# mimic4218.net
KiCad netlist of a schematic drawn in EAGLE
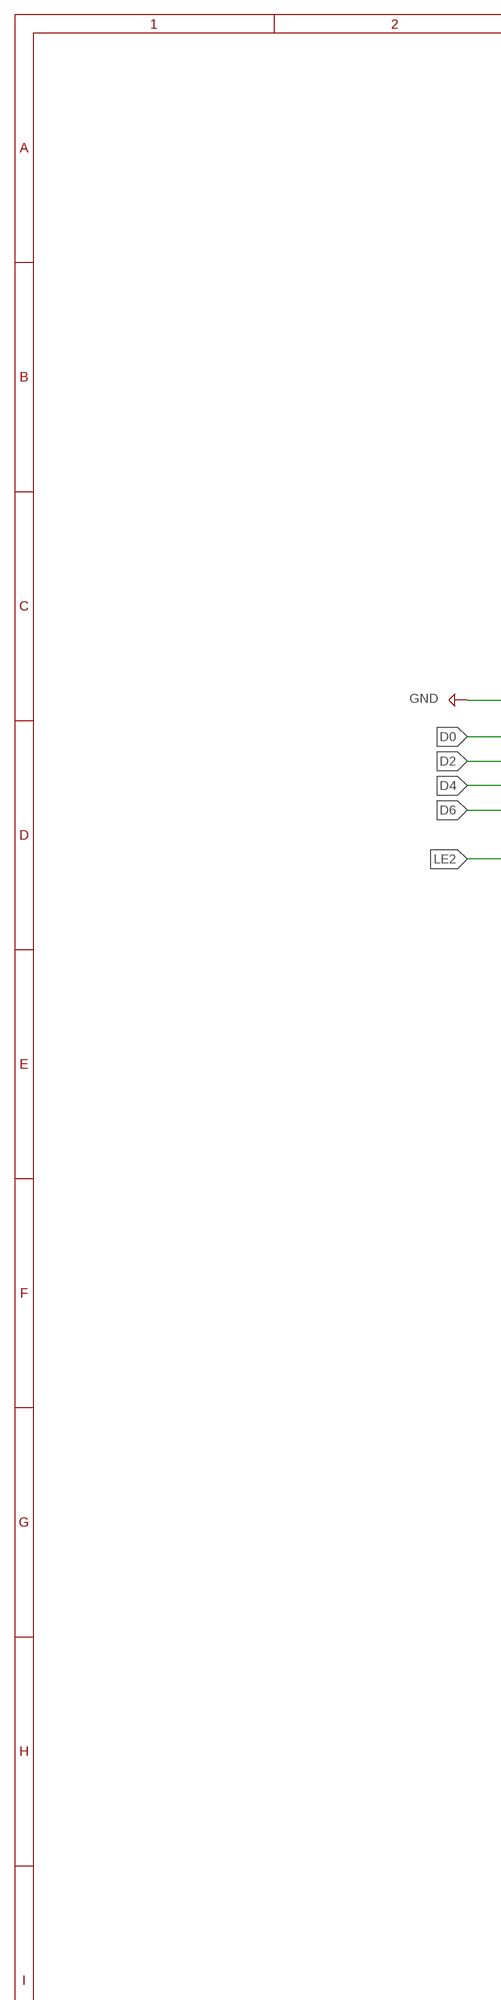
[diagram p0: schematic, sheet 1, part 1 of 2]
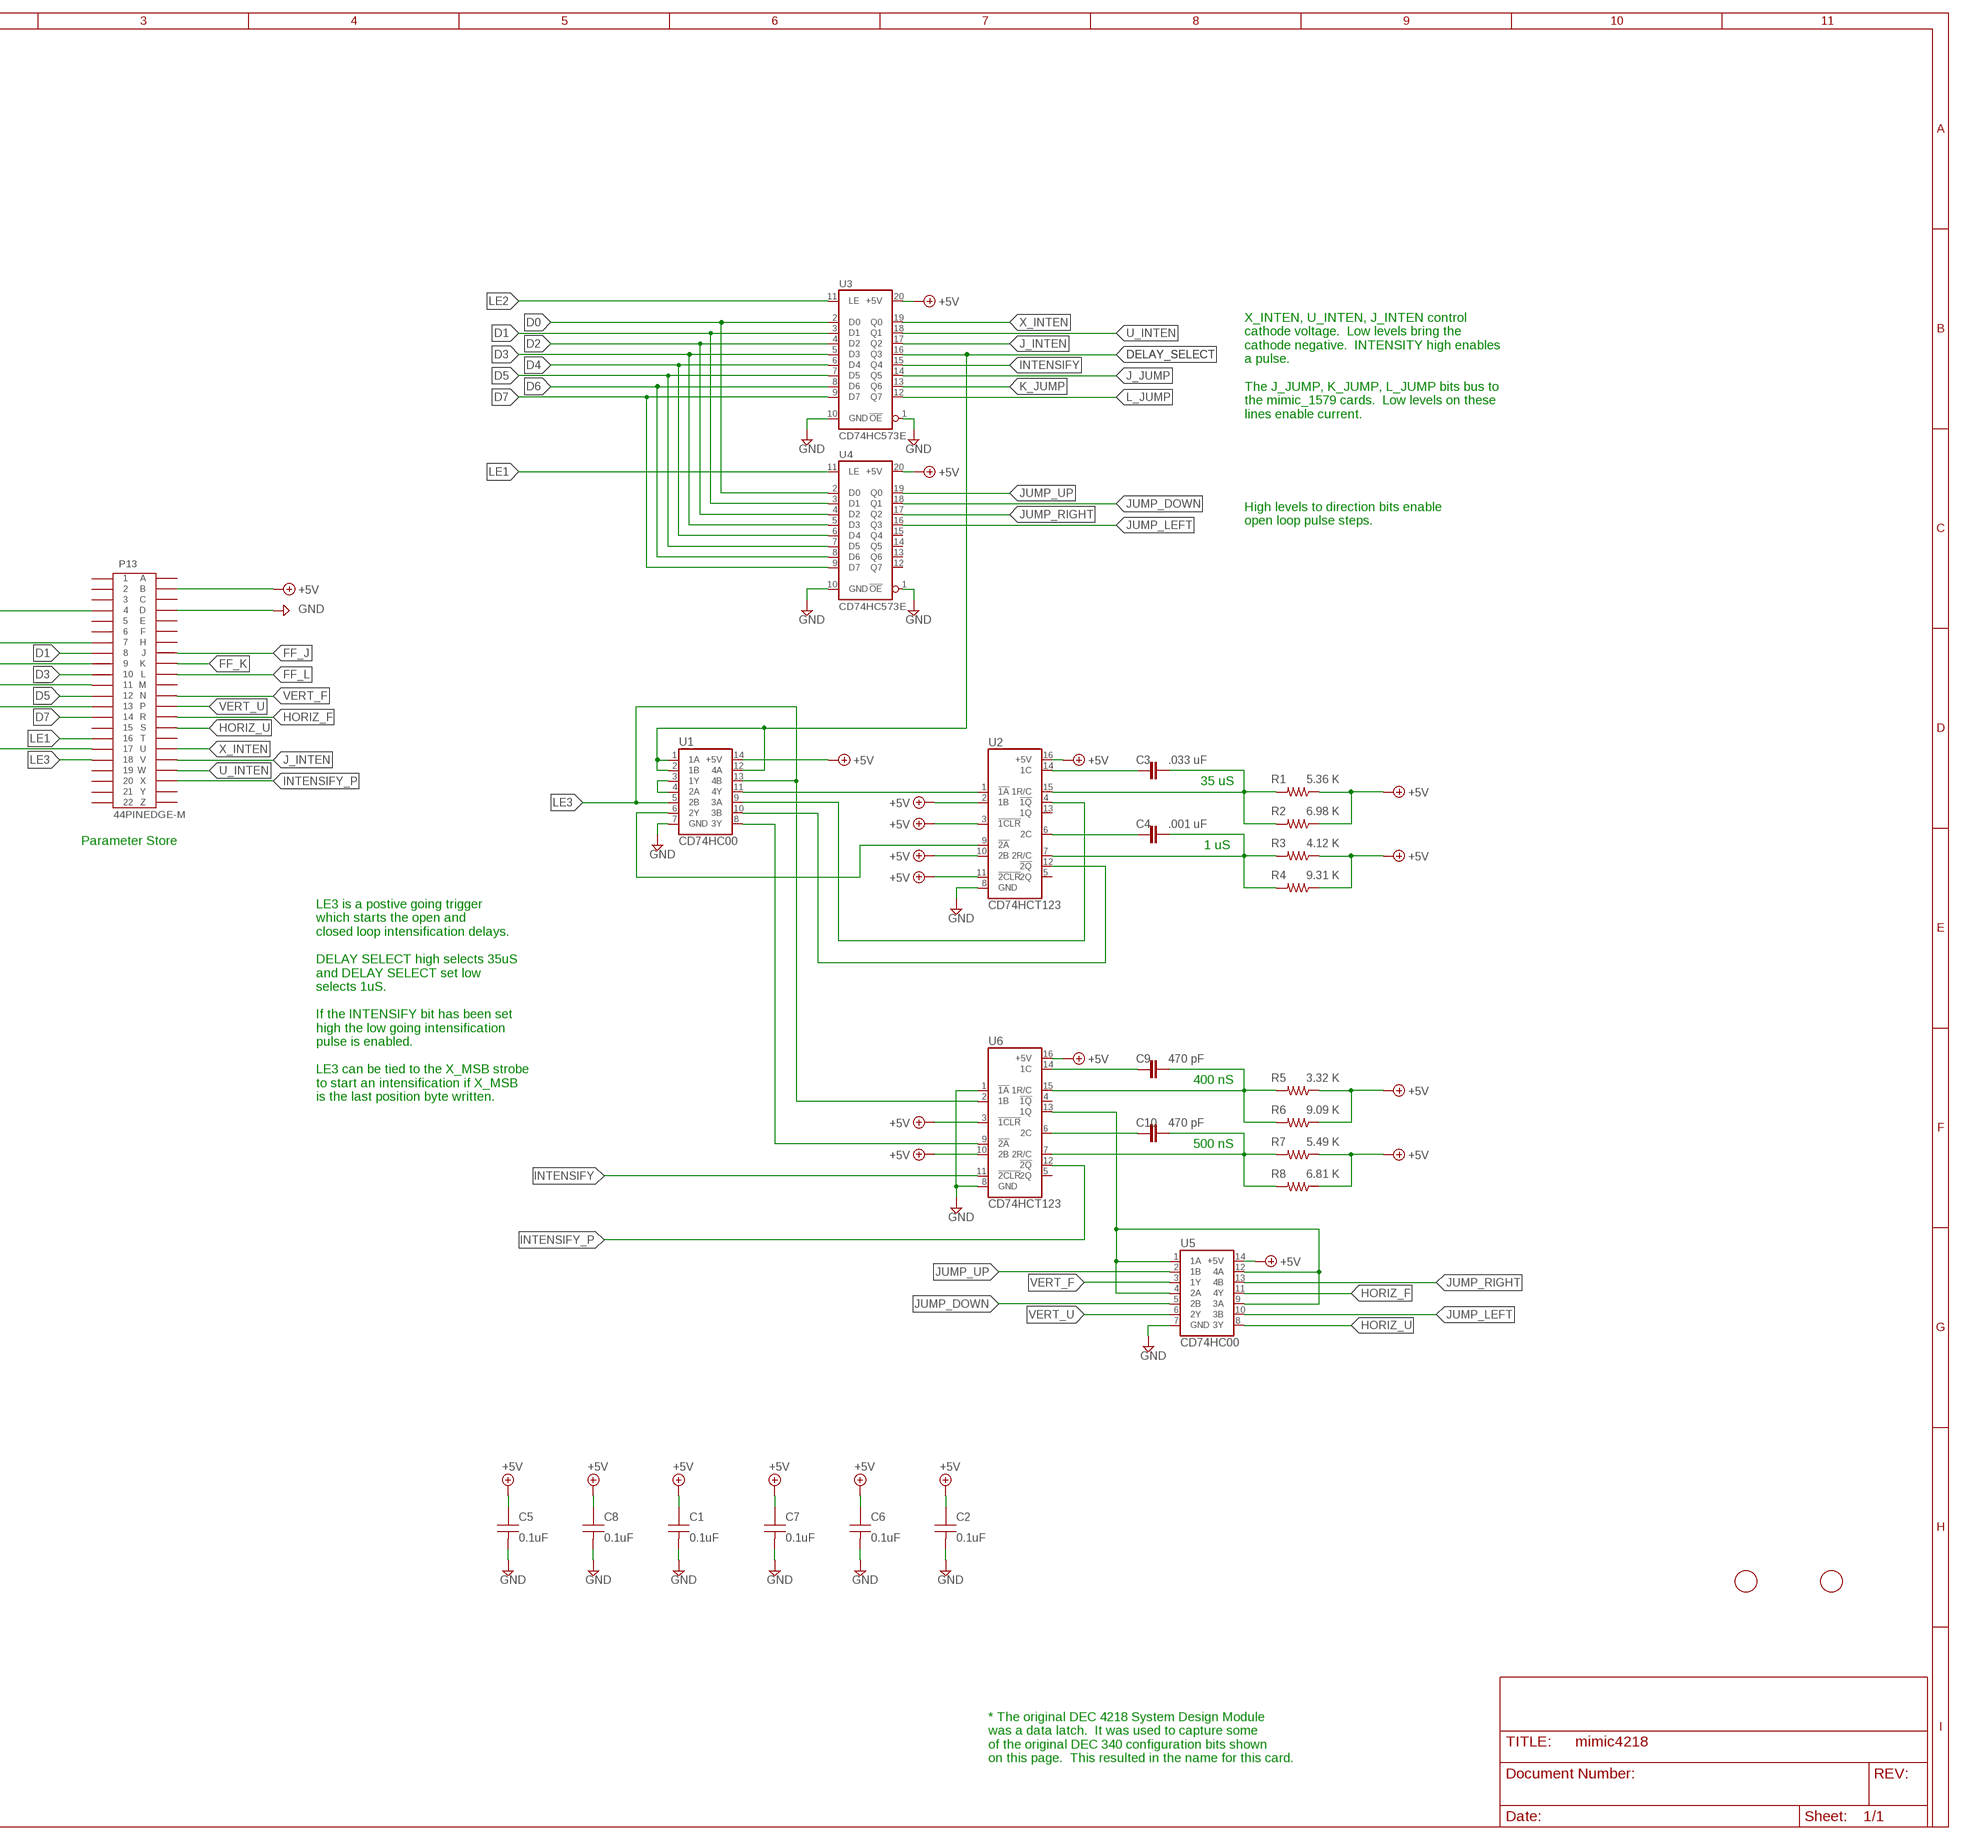
[diagram p1: schematic, sheet 1, part 2 of 2]

(export (version "E")
  (design (tool "Eeschema 10.0.6"))
  (components
    (comp (ref "C1")
      (value "0.1uF")
      (footprint "eagle-import:5MM_TH")
      (fields (field (name "MPN") "FA26X8R2A104KNU06"))
      (libsource (lib "eagle-import") (part "CAP0.1UF100V"))
    )
    (comp (ref "C2")
      (value "0.1uF")
      (footprint "eagle-import:5MM_TH")
      (fields (field (name "MPN") "FA26X8R2A104KNU06"))
      (libsource (lib "eagle-import") (part "CAP0.1UF100V"))
    )
    (comp (ref "C3")
      (value ".033 uF")
      (footprint "eagle-import:5MM_TH")
      (libsource (lib "eagle-import") (part "CAP_5MM"))
    )
    (comp (ref "C4")
      (value ".001 uF")
      (footprint "eagle-import:5MM_TH")
      (libsource (lib "eagle-import") (part "CAP_5MM"))
    )
    (comp (ref "C5")
      (value "0.1uF")
      (footprint "eagle-import:5MM_TH")
      (fields (field (name "MPN") "FA26X8R2A104KNU06"))
      (libsource (lib "eagle-import") (part "CAP0.1UF100V"))
    )
    (comp (ref "C6")
      (value "0.1uF")
      (footprint "eagle-import:5MM_TH")
      (fields (field (name "MPN") "FA26X8R2A104KNU06"))
      (libsource (lib "eagle-import") (part "CAP0.1UF100V"))
    )
    (comp (ref "C7")
      (value "0.1uF")
      (footprint "eagle-import:5MM_TH")
      (fields (field (name "MPN") "FA26X8R2A104KNU06"))
      (libsource (lib "eagle-import") (part "CAP0.1UF100V"))
    )
    (comp (ref "C8")
      (value "0.1uF")
      (footprint "eagle-import:5MM_TH")
      (fields (field (name "MPN") "FA26X8R2A104KNU06"))
      (libsource (lib "eagle-import") (part "CAP0.1UF100V"))
    )
    (comp (ref "C9")
      (value "470 pF")
      (footprint "eagle-import:5MM_TH")
      (libsource (lib "eagle-import") (part "CAP_5MM"))
    )
    (comp (ref "C10")
      (value "470 pF")
      (footprint "eagle-import:5MM_TH")
      (libsource (lib "eagle-import") (part "CAP_5MM"))
    )
    (comp (ref "P13")
      (value "44PINEDGE-M")
      (footprint "eagle-import:44PINEDGE")
      (libsource (lib "eagle-import") (part "44PINEDGE-M"))
    )
    (comp (ref "R1")
      (value "5.36 K")
      (footprint "eagle-import:0207_10")
      (libsource (lib "eagle-import") (part "R-1/4WATT"))
    )
    (comp (ref "R2")
      (value "6.98 K")
      (footprint "eagle-import:0207_10")
      (libsource (lib "eagle-import") (part "R-1/4WATT"))
    )
    (comp (ref "R3")
      (value "4.12 K")
      (footprint "eagle-import:0207_10")
      (libsource (lib "eagle-import") (part "R-1/4WATT"))
    )
    (comp (ref "R4")
      (value "9.31 K")
      (footprint "eagle-import:0207_10")
      (libsource (lib "eagle-import") (part "R-1/4WATT"))
    )
    (comp (ref "R5")
      (value "3.32 K")
      (footprint "eagle-import:0207_10")
      (libsource (lib "eagle-import") (part "R-1/4WATT"))
    )
    (comp (ref "R6")
      (value "9.09 K")
      (footprint "eagle-import:0207_10")
      (libsource (lib "eagle-import") (part "R-1/4WATT"))
    )
    (comp (ref "R7")
      (value "5.49 K")
      (footprint "eagle-import:0207_10")
      (libsource (lib "eagle-import") (part "R-1/4WATT"))
    )
    (comp (ref "R8")
      (value "6.81 K")
      (footprint "eagle-import:0207_10")
      (libsource (lib "eagle-import") (part "R-1/4WATT"))
    )
    (comp (ref "U$1")
      (value "FIDUCIAL")
      (footprint "eagle-import:FIDUCIAL_1MM")
      (libsource (lib "eagle-import") (part "FIDUCIAL"))
    )
    (comp (ref "U$2")
      (value "FIDUCIAL")
      (footprint "eagle-import:FIDUCIAL_1MM")
      (libsource (lib "eagle-import") (part "FIDUCIAL"))
    )
    (comp (ref "U1")
      (value "CD74HC00")
      (footprint "eagle-import:DIP-14")
      (libsource (lib "eagle-import") (part "CD74HC00"))
    )
    (comp (ref "U2")
      (value "CD74HCT123")
      (footprint "eagle-import:DIP-16")
      (libsource (lib "eagle-import") (part "CD74HCT123"))
    )
    (comp (ref "U3")
      (value "CD74HC573E")
      (footprint "eagle-import:DIP-20")
      (libsource (lib "eagle-import") (part "CD74HC573E"))
    )
    (comp (ref "U4")
      (value "CD74HC573E")
      (footprint "eagle-import:DIP-20")
      (libsource (lib "eagle-import") (part "CD74HC573E"))
    )
    (comp (ref "U5")
      (value "CD74HC00")
      (footprint "eagle-import:DIP-14")
      (libsource (lib "eagle-import") (part "CD74HC00"))
    )
    (comp (ref "U6")
      (value "CD74HCT123")
      (footprint "eagle-import:DIP-16")
      (libsource (lib "eagle-import") (part "CD74HCT123"))
    )
  )
  (nets
    (net (code "1") (name "+5V") (class "Default")
      (node (ref "C1") (pin "1") (pinfunction "1_1") (pintype "passive"))
      (node (ref "C2") (pin "1") (pinfunction "1_1") (pintype "passive"))
      (node (ref "C5") (pin "1") (pinfunction "1_1") (pintype "passive"))
      (node (ref "C6") (pin "1") (pinfunction "1_1") (pintype "passive"))
      (node (ref "C7") (pin "1") (pinfunction "1_1") (pintype "passive"))
      (node (ref "C8") (pin "1") (pinfunction "1_1") (pintype "passive"))
      (node (ref "P13") (pin "B") (pinfunction "B_B") (pintype "passive"))
      (node (ref "R1") (pin "1") (pinfunction "P$1_1") (pintype "passive"))
      (node (ref "R2") (pin "1") (pinfunction "P$1_1") (pintype "passive"))
      (node (ref "R3") (pin "1") (pinfunction "P$1_1") (pintype "passive"))
      (node (ref "R4") (pin "1") (pinfunction "P$1_1") (pintype "passive"))
      (node (ref "R5") (pin "1") (pinfunction "P$1_1") (pintype "passive"))
      (node (ref "R6") (pin "1") (pinfunction "P$1_1") (pintype "passive"))
      (node (ref "R7") (pin "1") (pinfunction "P$1_1") (pintype "passive"))
      (node (ref "R8") (pin "1") (pinfunction "P$1_1") (pintype "passive"))
      (node (ref "U1") (pin "14") (pinfunction "+5V_14") (pintype "power_in"))
      (node (ref "U2") (pin "10") (pinfunction "2B_10") (pintype "input"))
      (node (ref "U2") (pin "11") (pinfunction "~{2CLR}_11") (pintype "input"))
      (node (ref "U2") (pin "16") (pinfunction "+5V_16") (pintype "power_in"))
      (node (ref "U2") (pin "2") (pinfunction "1B_2") (pintype "input"))
      (node (ref "U2") (pin "3") (pinfunction "~{1CLR}_3") (pintype "input"))
      (node (ref "U3") (pin "20") (pinfunction "+5V_20") (pintype "power_in"))
      (node (ref "U4") (pin "20") (pinfunction "+5V_20") (pintype "power_in"))
      (node (ref "U5") (pin "14") (pinfunction "+5V_14") (pintype "power_in"))
      (node (ref "U6") (pin "10") (pinfunction "2B_10") (pintype "input"))
      (node (ref "U6") (pin "16") (pinfunction "+5V_16") (pintype "power_in"))
      (node (ref "U6") (pin "3") (pinfunction "~{1CLR}_3") (pintype "input"))
    )
    (net (code "2") (name "D0") (class "Default")
      (node (ref "P13") (pin "7") (pinfunction "7_7") (pintype "passive"))
      (node (ref "U3") (pin "2") (pinfunction "D0_2") (pintype "input"))
      (node (ref "U4") (pin "2") (pinfunction "D0_2") (pintype "input"))
    )
    (net (code "3") (name "D1") (class "Default")
      (node (ref "P13") (pin "8") (pinfunction "8_8") (pintype "passive"))
      (node (ref "U3") (pin "3") (pinfunction "D1_3") (pintype "input"))
      (node (ref "U4") (pin "3") (pinfunction "D1_3") (pintype "input"))
    )
    (net (code "4") (name "D2") (class "Default")
      (node (ref "P13") (pin "9") (pinfunction "9_9") (pintype "passive"))
      (node (ref "U3") (pin "4") (pinfunction "D2_4") (pintype "input"))
      (node (ref "U4") (pin "4") (pinfunction "D2_4") (pintype "input"))
    )
    (net (code "5") (name "D3") (class "Default")
      (node (ref "P13") (pin "10") (pinfunction "10_10") (pintype "passive"))
      (node (ref "U3") (pin "5") (pinfunction "D3_5") (pintype "input"))
      (node (ref "U4") (pin "5") (pinfunction "D3_5") (pintype "input"))
    )
    (net (code "6") (name "D4") (class "Default")
      (node (ref "P13") (pin "11") (pinfunction "11_11") (pintype "passive"))
      (node (ref "U3") (pin "6") (pinfunction "D4_6") (pintype "input"))
      (node (ref "U4") (pin "6") (pinfunction "D4_6") (pintype "input"))
    )
    (net (code "7") (name "D5") (class "Default")
      (node (ref "P13") (pin "12") (pinfunction "12_12") (pintype "passive"))
      (node (ref "U3") (pin "7") (pinfunction "D5_7") (pintype "input"))
      (node (ref "U4") (pin "7") (pinfunction "D5_7") (pintype "input"))
    )
    (net (code "8") (name "D6") (class "Default")
      (node (ref "P13") (pin "13") (pinfunction "13_13") (pintype "passive"))
      (node (ref "U3") (pin "8") (pinfunction "D6_8") (pintype "input"))
      (node (ref "U4") (pin "8") (pinfunction "D6_8") (pintype "input"))
    )
    (net (code "9") (name "D7") (class "Default")
      (node (ref "P13") (pin "14") (pinfunction "14_14") (pintype "passive"))
      (node (ref "U3") (pin "9") (pinfunction "D7_9") (pintype "input"))
      (node (ref "U4") (pin "9") (pinfunction "D7_9") (pintype "input"))
    )
    (net (code "10") (name "DELAY_SELECT") (class "Default")
      (node (ref "U1") (pin "1") (pinfunction "1A_1") (pintype "input"))
      (node (ref "U1") (pin "12") (pinfunction "4A_12") (pintype "input"))
      (node (ref "U1") (pin "2") (pinfunction "1B_2") (pintype "input"))
      (node (ref "U3") (pin "16") (pinfunction "Q3_16") (pintype "tri_state"))
    )
    (net (code "11") (name "FF_J") (class "Default")
      (node (ref "P13") (pin "J") (pinfunction "J_J") (pintype "passive"))
    )
    (net (code "12") (name "FF_K") (class "Default")
      (node (ref "P13") (pin "K") (pinfunction "K_K") (pintype "passive"))
    )
    (net (code "13") (name "FF_L") (class "Default")
      (node (ref "P13") (pin "L") (pinfunction "L_L") (pintype "passive"))
    )
    (net (code "14") (name "GND") (class "Default")
      (node (ref "C1") (pin "2") (pinfunction "2_2") (pintype "passive"))
      (node (ref "C2") (pin "2") (pinfunction "2_2") (pintype "passive"))
      (node (ref "C5") (pin "2") (pinfunction "2_2") (pintype "passive"))
      (node (ref "C6") (pin "2") (pinfunction "2_2") (pintype "passive"))
      (node (ref "C7") (pin "2") (pinfunction "2_2") (pintype "passive"))
      (node (ref "C8") (pin "2") (pinfunction "2_2") (pintype "passive"))
      (node (ref "P13") (pin "4") (pinfunction "4_4") (pintype "passive"))
      (node (ref "P13") (pin "D") (pinfunction "D_D") (pintype "passive"))
      (node (ref "U1") (pin "7") (pinfunction "GND_7") (pintype "power_in"))
      (node (ref "U2") (pin "8") (pinfunction "GND_8") (pintype "power_in"))
      (node (ref "U3") (pin "1") (pinfunction "~{OE}_1") (pintype "input"))
      (node (ref "U3") (pin "10") (pinfunction "GND_10") (pintype "power_in"))
      (node (ref "U4") (pin "1") (pinfunction "~{OE}_1") (pintype "input"))
      (node (ref "U4") (pin "10") (pinfunction "GND_10") (pintype "power_in"))
      (node (ref "U5") (pin "7") (pinfunction "GND_7") (pintype "power_in"))
      (node (ref "U6") (pin "1") (pinfunction "~{1A}_1") (pintype "input"))
      (node (ref "U6") (pin "8") (pinfunction "GND_8") (pintype "power_in"))
    )
    (net (code "15") (name "HORIZ_F") (class "Default")
      (node (ref "P13") (pin "R") (pinfunction "R_R") (pintype "passive"))
      (node (ref "U5") (pin "11") (pinfunction "4Y_11") (pintype "output"))
    )
    (net (code "16") (name "HORIZ_U") (class "Default")
      (node (ref "P13") (pin "S") (pinfunction "S_S") (pintype "passive"))
      (node (ref "U5") (pin "8") (pinfunction "3Y_8") (pintype "output"))
    )
    (net (code "17") (name "INTENSIFY") (class "Default")
      (node (ref "U3") (pin "15") (pinfunction "Q4_15") (pintype "tri_state"))
      (node (ref "U6") (pin "11") (pinfunction "~{2CLR}_11") (pintype "input"))
    )
    (net (code "18") (name "INTENSIFY_P") (class "Default")
      (node (ref "P13") (pin "X") (pinfunction "X_X") (pintype "passive"))
      (node (ref "U6") (pin "12") (pinfunction "~{2Q}_12") (pintype "output"))
    )
    (net (code "19") (name "JUMP_DOWN") (class "Default")
      (node (ref "U4") (pin "18") (pinfunction "Q1_18") (pintype "tri_state"))
      (node (ref "U5") (pin "5") (pinfunction "2B_5") (pintype "input"))
    )
    (net (code "20") (name "JUMP_LEFT") (class "Default")
      (node (ref "U4") (pin "16") (pinfunction "Q3_16") (pintype "tri_state"))
      (node (ref "U5") (pin "10") (pinfunction "3B_10") (pintype "input"))
    )
    (net (code "21") (name "JUMP_RIGHT") (class "Default")
      (node (ref "U4") (pin "17") (pinfunction "Q2_17") (pintype "tri_state"))
      (node (ref "U5") (pin "13") (pinfunction "4B_13") (pintype "input"))
    )
    (net (code "22") (name "JUMP_UP") (class "Default")
      (node (ref "U4") (pin "19") (pinfunction "Q0_19") (pintype "tri_state"))
      (node (ref "U5") (pin "2") (pinfunction "1B_2") (pintype "input"))
    )
    (net (code "23") (name "J_INTEN") (class "Default")
      (node (ref "P13") (pin "V") (pinfunction "V_V") (pintype "passive"))
      (node (ref "U3") (pin "17") (pinfunction "Q2_17") (pintype "tri_state"))
    )
    (net (code "24") (name "J_JUMP") (class "Default")
      (node (ref "U3") (pin "14") (pinfunction "Q5_14") (pintype "tri_state"))
    )
    (net (code "25") (name "K_JUMP") (class "Default")
      (node (ref "U3") (pin "13") (pinfunction "Q6_13") (pintype "tri_state"))
    )
    (net (code "26") (name "LE1") (class "Default")
      (node (ref "P13") (pin "16") (pinfunction "16_16") (pintype "passive"))
      (node (ref "U4") (pin "11") (pinfunction "LE_11") (pintype "input"))
    )
    (net (code "27") (name "LE2") (class "Default")
      (node (ref "P13") (pin "17") (pinfunction "17_17") (pintype "passive"))
      (node (ref "U3") (pin "11") (pinfunction "LE_11") (pintype "input"))
    )
    (net (code "28") (name "LE3") (class "Default")
      (node (ref "P13") (pin "18") (pinfunction "18_18") (pintype "passive"))
      (node (ref "U1") (pin "13") (pinfunction "4B_13") (pintype "input"))
      (node (ref "U1") (pin "5") (pinfunction "2B_5") (pintype "input"))
      (node (ref "U6") (pin "2") (pinfunction "1B_2") (pintype "input"))
    )
    (net (code "29") (name "L_JUMP") (class "Default")
      (node (ref "U3") (pin "12") (pinfunction "Q7_12") (pintype "tri_state"))
    )
    (net (code "30") (name "Net-(R1-P$2)") (class "Default")
      (node (ref "C3") (pin "2") (pinfunction "2_2") (pintype "passive"))
      (node (ref "R1") (pin "2") (pinfunction "P$2_2") (pintype "passive"))
      (node (ref "R2") (pin "2") (pinfunction "P$2_2") (pintype "passive"))
      (node (ref "U2") (pin "15") (pinfunction "1R/C_15") (pintype "passive"))
    )
    (net (code "31") (name "Net-(R3-P$2)") (class "Default")
      (node (ref "C4") (pin "2") (pinfunction "2_2") (pintype "passive"))
      (node (ref "R3") (pin "2") (pinfunction "P$2_2") (pintype "passive"))
      (node (ref "R4") (pin "2") (pinfunction "P$2_2") (pintype "passive"))
      (node (ref "U2") (pin "7") (pinfunction "2R/C_7") (pintype "passive"))
    )
    (net (code "32") (name "Net-(R5-P$2)") (class "Default")
      (node (ref "C9") (pin "2") (pinfunction "2_2") (pintype "passive"))
      (node (ref "R5") (pin "2") (pinfunction "P$2_2") (pintype "passive"))
      (node (ref "R6") (pin "2") (pinfunction "P$2_2") (pintype "passive"))
      (node (ref "U6") (pin "15") (pinfunction "1R/C_15") (pintype "passive"))
    )
    (net (code "33") (name "Net-(R7-P$2)") (class "Default")
      (node (ref "C10") (pin "2") (pinfunction "2_2") (pintype "passive"))
      (node (ref "R7") (pin "2") (pinfunction "P$2_2") (pintype "passive"))
      (node (ref "R8") (pin "2") (pinfunction "P$2_2") (pintype "passive"))
      (node (ref "U6") (pin "7") (pinfunction "2R/C_7") (pintype "passive"))
    )
    (net (code "34") (name "Net-(U1-1Y)") (class "Default")
      (node (ref "U1") (pin "3") (pinfunction "1Y_3") (pintype "output"))
      (node (ref "U1") (pin "4") (pinfunction "2A_4") (pintype "input"))
    )
    (net (code "35") (name "Net-(U1-2Y)") (class "Default")
      (node (ref "U1") (pin "6") (pinfunction "2Y_6") (pintype "output"))
      (node (ref "U2") (pin "9") (pinfunction "~{2A}_9") (pintype "input"))
    )
    (net (code "36") (name "Net-(U1-3A)") (class "Default")
      (node (ref "U1") (pin "9") (pinfunction "3A_9") (pintype "input"))
      (node (ref "U2") (pin "4") (pinfunction "~{1Q}_4") (pintype "output"))
    )
    (net (code "37") (name "Net-(U1-3B)") (class "Default")
      (node (ref "U1") (pin "10") (pinfunction "3B_10") (pintype "input"))
      (node (ref "U2") (pin "12") (pinfunction "~{2Q}_12") (pintype "output"))
    )
    (net (code "38") (name "Net-(U1-3Y)") (class "Default")
      (node (ref "U1") (pin "8") (pinfunction "3Y_8") (pintype "output"))
      (node (ref "U6") (pin "9") (pinfunction "~{2A}_9") (pintype "input"))
    )
    (net (code "39") (name "Net-(U1-4Y)") (class "Default")
      (node (ref "U1") (pin "11") (pinfunction "4Y_11") (pintype "output"))
      (node (ref "U2") (pin "1") (pinfunction "~{1A}_1") (pintype "input"))
    )
    (net (code "40") (name "Net-(U2-1C)") (class "Default")
      (node (ref "C3") (pin "1") (pinfunction "1_1") (pintype "passive"))
      (node (ref "U2") (pin "14") (pinfunction "1C_14") (pintype "passive"))
    )
    (net (code "41") (name "Net-(U2-2C)") (class "Default")
      (node (ref "C4") (pin "1") (pinfunction "1_1") (pintype "passive"))
      (node (ref "U2") (pin "6") (pinfunction "2C_6") (pintype "passive"))
    )
    (net (code "42") (name "Net-(U5-1A)") (class "Default")
      (node (ref "U5") (pin "1") (pinfunction "1A_1") (pintype "input"))
      (node (ref "U5") (pin "12") (pinfunction "4A_12") (pintype "input"))
      (node (ref "U5") (pin "4") (pinfunction "2A_4") (pintype "input"))
      (node (ref "U5") (pin "9") (pinfunction "3A_9") (pintype "input"))
      (node (ref "U6") (pin "13") (pinfunction "1Q_13") (pintype "output"))
    )
    (net (code "43") (name "Net-(U6-1C)") (class "Default")
      (node (ref "C9") (pin "1") (pinfunction "1_1") (pintype "passive"))
      (node (ref "U6") (pin "14") (pinfunction "1C_14") (pintype "passive"))
    )
    (net (code "44") (name "Net-(U6-2C)") (class "Default")
      (node (ref "C10") (pin "1") (pinfunction "1_1") (pintype "passive"))
      (node (ref "U6") (pin "6") (pinfunction "2C_6") (pintype "passive"))
    )
    (net (code "45") (name "U_INTEN") (class "Default")
      (node (ref "P13") (pin "W") (pinfunction "W_W") (pintype "passive"))
      (node (ref "U3") (pin "18") (pinfunction "Q1_18") (pintype "tri_state"))
    )
    (net (code "46") (name "VERT_F") (class "Default")
      (node (ref "P13") (pin "N") (pinfunction "N_N") (pintype "passive"))
      (node (ref "U5") (pin "3") (pinfunction "1Y_3") (pintype "output"))
    )
    (net (code "47") (name "VERT_U") (class "Default")
      (node (ref "P13") (pin "P") (pinfunction "P_P") (pintype "passive"))
      (node (ref "U5") (pin "6") (pinfunction "2Y_6") (pintype "output"))
    )
    (net (code "48") (name "X_INTEN") (class "Default")
      (node (ref "P13") (pin "U") (pinfunction "U_U") (pintype "passive"))
      (node (ref "U3") (pin "19") (pinfunction "Q0_19") (pintype "tri_state"))
    )
    (net (code "49") (name "unconnected-(P13-Pad1)") (class "Default")
      (node (ref "P13") (pin "1") (pinfunction "1_1") (pintype "passive"))
    )
    (net (code "50") (name "unconnected-(P13-Pad2)") (class "Default")
      (node (ref "P13") (pin "2") (pinfunction "2_2") (pintype "passive"))
    )
    (net (code "51") (name "unconnected-(P13-Pad3)") (class "Default")
      (node (ref "P13") (pin "3") (pinfunction "3_3") (pintype "passive"))
    )
    (net (code "52") (name "unconnected-(P13-Pad5)") (class "Default")
      (node (ref "P13") (pin "5") (pinfunction "5_5") (pintype "passive"))
    )
    (net (code "53") (name "unconnected-(P13-Pad6)") (class "Default")
      (node (ref "P13") (pin "6") (pinfunction "6_6") (pintype "passive"))
    )
    (net (code "54") (name "unconnected-(P13-Pad15)") (class "Default")
      (node (ref "P13") (pin "15") (pinfunction "15_15") (pintype "passive"))
    )
    (net (code "55") (name "unconnected-(P13-Pad19)") (class "Default")
      (node (ref "P13") (pin "19") (pinfunction "19_19") (pintype "passive"))
    )
    (net (code "56") (name "unconnected-(P13-Pad20)") (class "Default")
      (node (ref "P13") (pin "20") (pinfunction "20_20") (pintype "passive"))
    )
    (net (code "57") (name "unconnected-(P13-Pad21)") (class "Default")
      (node (ref "P13") (pin "21") (pinfunction "21_21") (pintype "passive"))
    )
    (net (code "58") (name "unconnected-(P13-Pad22)") (class "Default")
      (node (ref "P13") (pin "22") (pinfunction "22_22") (pintype "passive"))
    )
    (net (code "59") (name "unconnected-(P13-PadA)") (class "Default")
      (node (ref "P13") (pin "A") (pinfunction "A_A") (pintype "passive"))
    )
    (net (code "60") (name "unconnected-(P13-PadC)") (class "Default")
      (node (ref "P13") (pin "C") (pinfunction "C_C") (pintype "passive"))
    )
    (net (code "61") (name "unconnected-(P13-PadE)") (class "Default")
      (node (ref "P13") (pin "E") (pinfunction "E_E") (pintype "passive"))
    )
    (net (code "62") (name "unconnected-(P13-PadF)") (class "Default")
      (node (ref "P13") (pin "F") (pinfunction "F_F") (pintype "passive"))
    )
    (net (code "63") (name "unconnected-(P13-PadH)") (class "Default")
      (node (ref "P13") (pin "H") (pinfunction "H_H") (pintype "passive"))
    )
    (net (code "64") (name "unconnected-(P13-PadM)") (class "Default")
      (node (ref "P13") (pin "M") (pinfunction "M_M") (pintype "passive"))
    )
    (net (code "65") (name "unconnected-(P13-PadT)") (class "Default")
      (node (ref "P13") (pin "T") (pinfunction "T_T") (pintype "passive"))
    )
    (net (code "66") (name "unconnected-(P13-PadY)") (class "Default")
      (node (ref "P13") (pin "Y") (pinfunction "Y_Y") (pintype "passive"))
    )
    (net (code "67") (name "unconnected-(P13-PadZ)") (class "Default")
      (node (ref "P13") (pin "Z") (pinfunction "Z_Z") (pintype "passive"))
    )
    (net (code "68") (name "unconnected-(U2-1Q-Pad13)") (class "Default")
      (node (ref "U2") (pin "13") (pinfunction "1Q_13") (pintype "output"))
    )
    (net (code "69") (name "unconnected-(U2-2Q-Pad5)") (class "Default")
      (node (ref "U2") (pin "5") (pinfunction "2Q_5") (pintype "output"))
    )
    (net (code "70") (name "unconnected-(U4-Q4-Pad15)") (class "Default")
      (node (ref "U4") (pin "15") (pinfunction "Q4_15") (pintype "tri_state"))
    )
    (net (code "71") (name "unconnected-(U4-Q5-Pad14)") (class "Default")
      (node (ref "U4") (pin "14") (pinfunction "Q5_14") (pintype "tri_state"))
    )
    (net (code "72") (name "unconnected-(U4-Q6-Pad13)") (class "Default")
      (node (ref "U4") (pin "13") (pinfunction "Q6_13") (pintype "tri_state"))
    )
    (net (code "73") (name "unconnected-(U4-Q7-Pad12)") (class "Default")
      (node (ref "U4") (pin "12") (pinfunction "Q7_12") (pintype "tri_state"))
    )
    (net (code "74") (name "unconnected-(U6-2Q-Pad5)") (class "Default")
      (node (ref "U6") (pin "5") (pinfunction "2Q_5") (pintype "output"))
    )
    (net (code "75") (name "unconnected-(U6-~{1Q}-Pad4)") (class "Default")
      (node (ref "U6") (pin "4") (pinfunction "~{1Q}_4") (pintype "output"))
    )
  )
)
